# Adafruit_Pro_Trinket_5v0.net
KiCad netlist of a schematic drawn in EAGLE
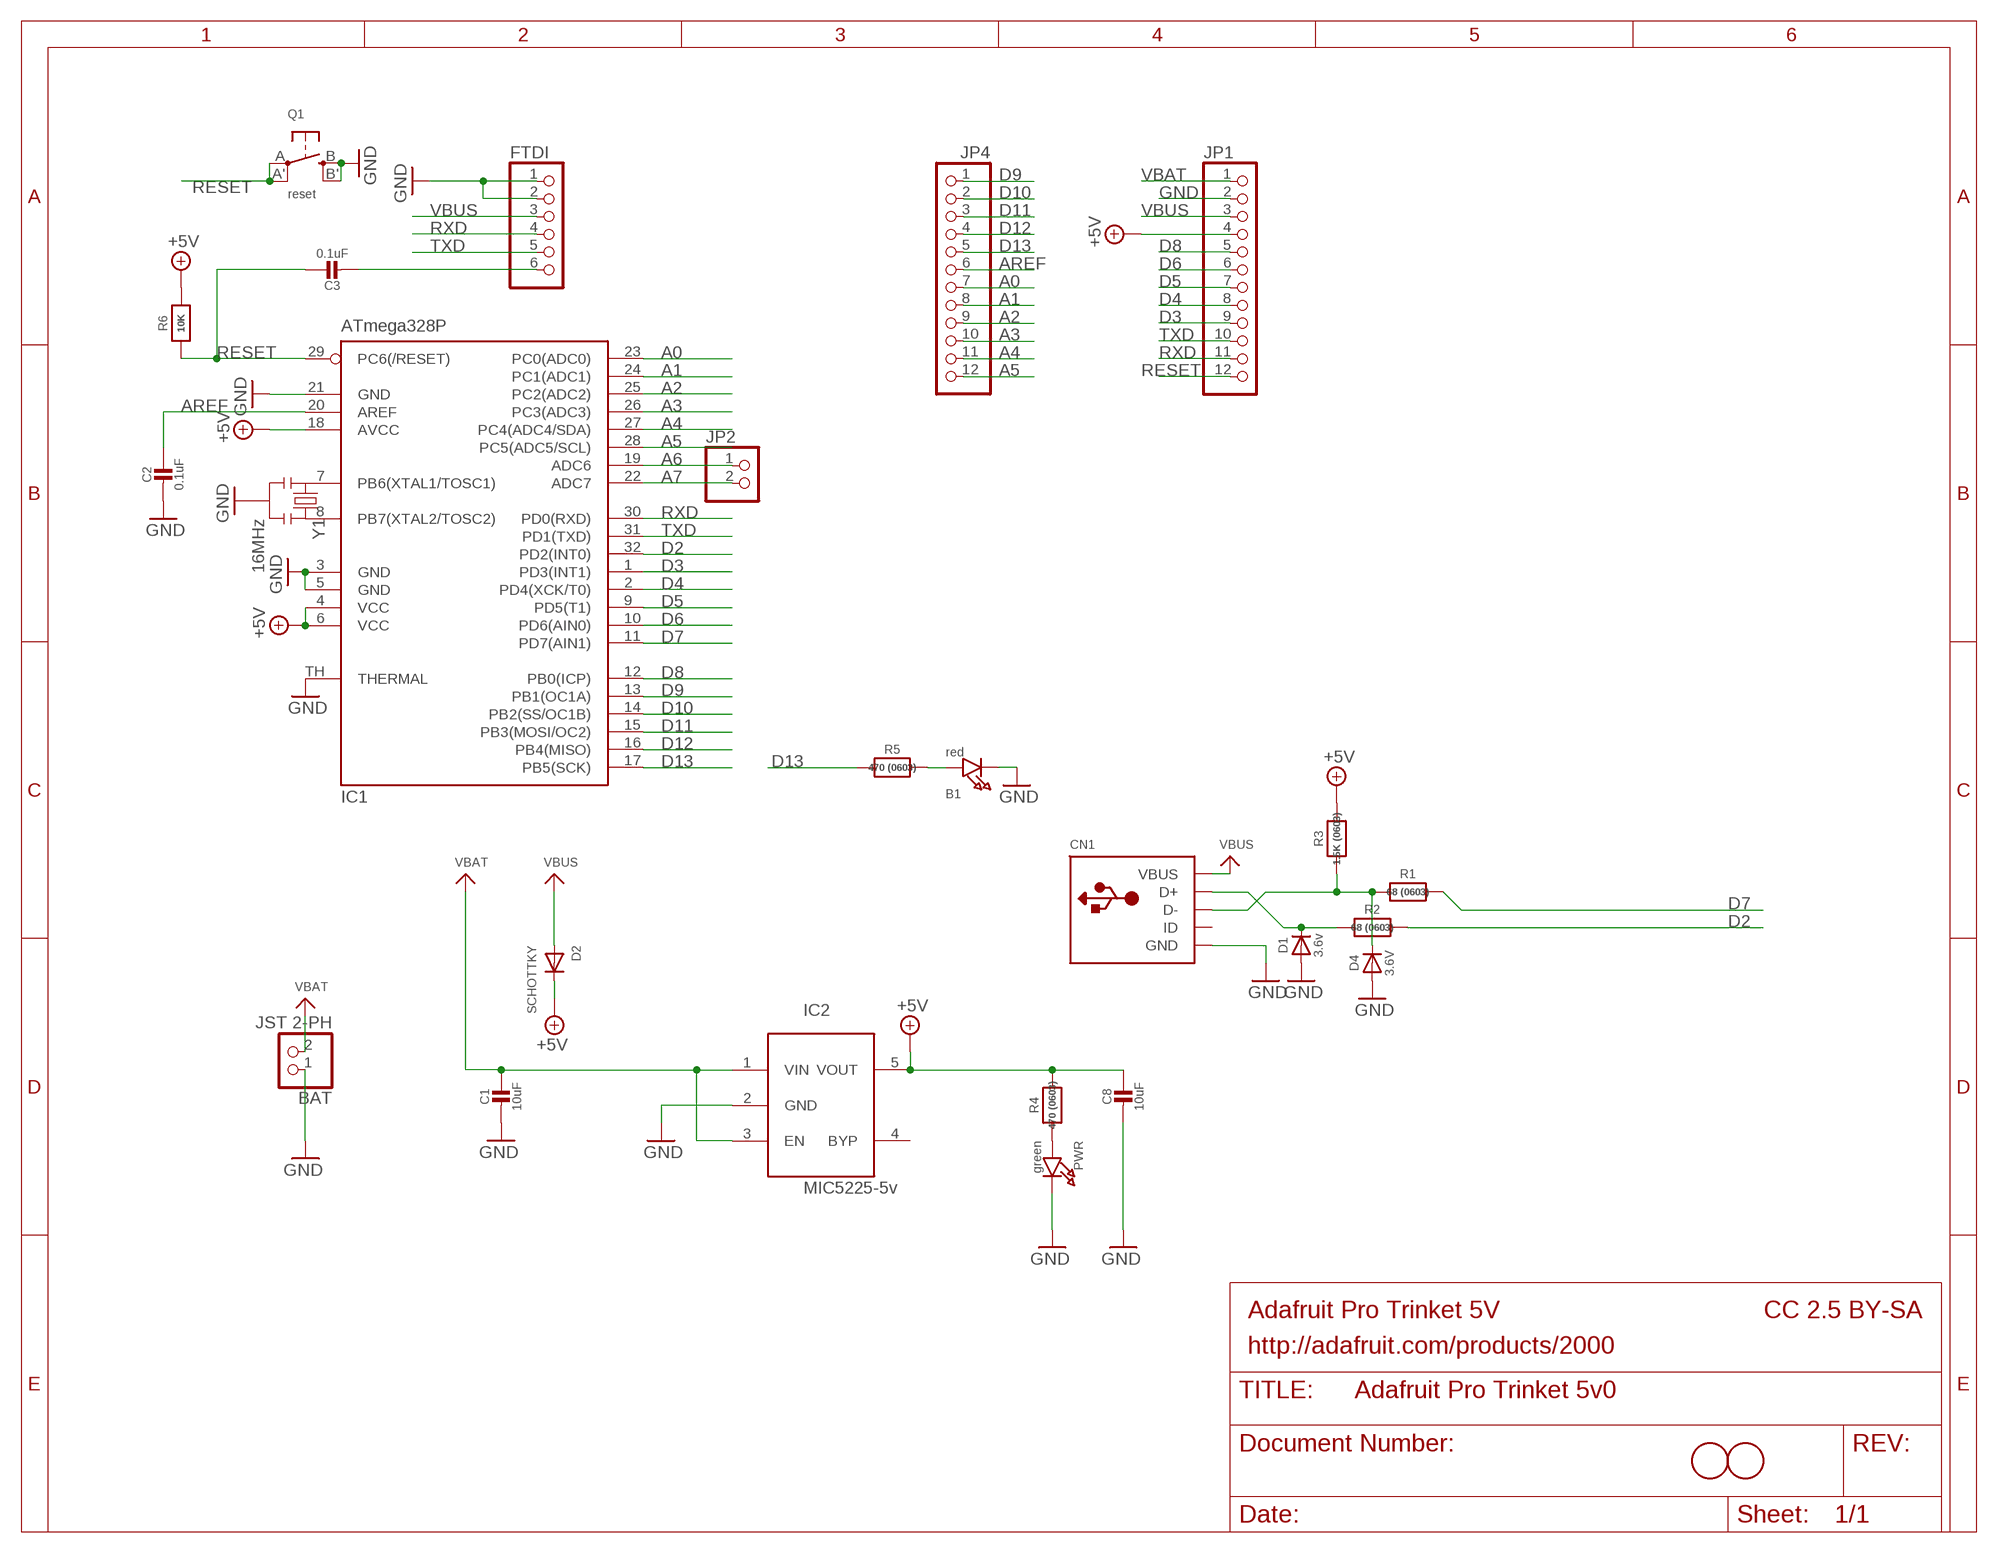
[diagram p0: schematic, sheet 1]

(export (version "E")
  (design (tool "Eeschema 10.0.6"))
  (components
    (comp (ref "B1")
      (value "red")
      (footprint "eagle-import:CHIPLED_0805_NOOUTLINE")
      (libsource (lib "eagle-import") (part "LED0805_NOOUTLINE"))
    )
    (comp (ref "BAT")
      (value "JST 2-PH")
      (footprint "eagle-import:JSTPH2")
      (libsource (lib "eagle-import") (part "CON_JST_PH_2PIN"))
    )
    (comp (ref "C1")
      (value "10uF")
      (footprint "eagle-import:0805-NO")
      (libsource (lib "eagle-import") (part "CAP_CERAMIC0805-NOOUTLINE"))
    )
    (comp (ref "C2")
      (value "0.1uF")
      (footprint "eagle-import:_0805MP")
      (libsource (lib "eagle-import") (part "CAP_CERAMIC_0805MP"))
    )
    (comp (ref "C3")
      (value "0.1uF")
      (footprint "eagle-import:0805-NO")
      (libsource (lib "eagle-import") (part "CAP_CERAMIC0805-NOOUTLINE"))
    )
    (comp (ref "C8")
      (value "10uF")
      (footprint "eagle-import:0805-NO")
      (libsource (lib "eagle-import") (part "CAP_CERAMIC0805-NOOUTLINE"))
    )
    (comp (ref "CN1")
      (value "USBMICRO_20329")
      (footprint "eagle-import:4UCONN_20329")
      (libsource (lib "eagle-import") (part "USBMICRO_20329"))
    )
    (comp (ref "D1")
      (value "3.6v")
      (footprint "eagle-import:SOD-323")
      (libsource (lib "eagle-import") (part "DIODESOD-323"))
    )
    (comp (ref "D2")
      (value "SCHOTTKY")
      (footprint "eagle-import:SOD-123FL")
      (libsource (lib "eagle-import") (part "DIODE_SOD-123FL"))
    )
    (comp (ref "D4")
      (value "3.6V")
      (footprint "eagle-import:SOD-323")
      (libsource (lib "eagle-import") (part "DIODESOD-323"))
    )
    (comp (ref "FTDI")
      (value "PINHD-1X6CB")
      (footprint "eagle-import:1X06-CLEANBIG")
      (libsource (lib "eagle-import") (part "PINHD-1X6CB"))
    )
    (comp (ref "IC1")
      (value "ATmega328P")
      (footprint "eagle-import:MLF32-TH")
      (fields (field (name "MPN") "ATMEGA88PA-MU"))
      (libsource (lib "eagle-import") (part "MEGA8-MI"))
    )
    (comp (ref "IC2")
      (value "MIC5225-5v")
      (footprint "eagle-import:SOT23-5L")
      (libsource (lib "eagle-import") (part "LP298XS"))
    )
    (comp (ref "JP1")
      (value "PINHD-1X12-CB")
      (footprint "eagle-import:1X12-CB")
      (libsource (lib "eagle-import") (part "PINHD-1X12-CB"))
    )
    (comp (ref "JP2")
      (value "HEADER-1X2ROUND")
      (footprint "eagle-import:1X02_ROUND")
      (libsource (lib "eagle-import") (part "HEADER-1X2ROUND"))
    )
    (comp (ref "JP4")
      (value "PINHD-1X12-CB")
      (footprint "eagle-import:1X12-CB")
      (libsource (lib "eagle-import") (part "PINHD-1X12-CB"))
    )
    (comp (ref "PWR")
      (value "green")
      (footprint "eagle-import:CHIPLED_0805_NOOUTLINE")
      (libsource (lib "eagle-import") (part "LED0805_NOOUTLINE"))
    )
    (comp (ref "Q1")
      (value "reset")
      (footprint "eagle-import:BTN_KMR2_4.6X2.8")
      (libsource (lib "eagle-import") (part "SWITCH_TACT_SMT4.6X2.8"))
    )
    (comp (ref "R1")
      (value "68 (0603)")
      (footprint "eagle-import:0603-NO")
      (libsource (lib "eagle-import") (part "RESISTOR_0603_NOOUT"))
    )
    (comp (ref "R2")
      (value "68 (0603)")
      (footprint "eagle-import:0603-NO")
      (libsource (lib "eagle-import") (part "RESISTOR_0603_NOOUT"))
    )
    (comp (ref "R3")
      (value "1.5K (0603)")
      (footprint "eagle-import:0603-NO")
      (libsource (lib "eagle-import") (part "RESISTOR_0603_NOOUT"))
    )
    (comp (ref "R4")
      (value "470 (0603)")
      (footprint "eagle-import:0603-NO")
      (libsource (lib "eagle-import") (part "RESISTOR_0603_NOOUT"))
    )
    (comp (ref "R5")
      (value "470 (0603)")
      (footprint "eagle-import:0603-NO")
      (libsource (lib "eagle-import") (part "RESISTOR_0603_NOOUT"))
    )
    (comp (ref "R6")
      (value "10K")
      (footprint "eagle-import:0805-NO")
      (libsource (lib "eagle-import") (part "RESISTOR0805_NOOUTLINE"))
    )
    (comp (ref "U$1")
      (value "FIDUCIAL")
      (footprint "eagle-import:FIDUCIAL_1MM")
      (libsource (lib "eagle-import") (part "FIDUCIAL"))
    )
    (comp (ref "U$6")
      (value "FIDUCIAL")
      (footprint "eagle-import:FIDUCIAL_1MM")
      (libsource (lib "eagle-import") (part "FIDUCIAL"))
    )
    (comp (ref "Y1")
      (value "16MHz")
      (footprint "eagle-import:RESONATOR-SMD")
      (libsource (lib "eagle-import") (part "RESONATORSMD"))
    )
  )
  (nets
    (net (code "1") (name "+5V") (class "Default")
      (node (ref "C8") (pin "1") (pinfunction "1_1") (pintype "passive"))
      (node (ref "D2") (pin "C") (pinfunction "C_C") (pintype "passive"))
      (node (ref "IC1") (pin "18") (pinfunction "AVCC_18") (pintype "power_in"))
      (node (ref "IC1") (pin "4") (pinfunction "VCC_4") (pintype "power_in"))
      (node (ref "IC1") (pin "6") (pinfunction "VCC_6") (pintype "power_in"))
      (node (ref "IC2") (pin "5") (pinfunction "VOUT_5") (pintype "bidirectional"))
      (node (ref "JP1") (pin "4") (pinfunction "4_4") (pintype "passive"))
      (node (ref "R3") (pin "2") (pinfunction "2_2") (pintype "passive"))
      (node (ref "R4") (pin "2") (pinfunction "2_2") (pintype "passive"))
      (node (ref "R6") (pin "2") (pinfunction "2_2") (pintype "passive"))
    )
    (net (code "2") (name "/A0") (class "Default")
      (node (ref "IC1") (pin "23") (pinfunction "PC0(ADC0)_23") (pintype "bidirectional"))
      (node (ref "JP4") (pin "7") (pinfunction "7_7") (pintype "passive"))
    )
    (net (code "3") (name "/A1") (class "Default")
      (node (ref "IC1") (pin "24") (pinfunction "PC1(ADC1)_24") (pintype "bidirectional"))
      (node (ref "JP4") (pin "8") (pinfunction "8_8") (pintype "passive"))
    )
    (net (code "4") (name "/A2") (class "Default")
      (node (ref "IC1") (pin "25") (pinfunction "PC2(ADC2)_25") (pintype "bidirectional"))
      (node (ref "JP4") (pin "9") (pinfunction "9_9") (pintype "passive"))
    )
    (net (code "5") (name "/A3") (class "Default")
      (node (ref "IC1") (pin "26") (pinfunction "PC3(ADC3)_26") (pintype "bidirectional"))
      (node (ref "JP4") (pin "10") (pinfunction "10_10") (pintype "passive"))
    )
    (net (code "6") (name "/A4") (class "Default")
      (node (ref "IC1") (pin "27") (pinfunction "PC4(ADC4/SDA)_27") (pintype "bidirectional"))
      (node (ref "JP4") (pin "11") (pinfunction "11_11") (pintype "passive"))
    )
    (net (code "7") (name "/A5") (class "Default")
      (node (ref "IC1") (pin "28") (pinfunction "PC5(ADC5/SCL)_28") (pintype "bidirectional"))
      (node (ref "JP4") (pin "12") (pinfunction "12_12") (pintype "passive"))
    )
    (net (code "8") (name "/A6") (class "Default")
      (node (ref "IC1") (pin "19") (pinfunction "ADC6_19") (pintype "bidirectional"))
      (node (ref "JP2") (pin "1") (pinfunction "1_1") (pintype "passive"))
    )
    (net (code "9") (name "/A7") (class "Default")
      (node (ref "IC1") (pin "22") (pinfunction "ADC7_22") (pintype "bidirectional"))
      (node (ref "JP2") (pin "2") (pinfunction "2_2") (pintype "passive"))
    )
    (net (code "10") (name "/AREF") (class "Default")
      (node (ref "C2") (pin "1") (pinfunction "1_1") (pintype "passive"))
      (node (ref "IC1") (pin "20") (pinfunction "AREF_20") (pintype "passive"))
      (node (ref "JP4") (pin "6") (pinfunction "6_6") (pintype "passive"))
    )
    (net (code "11") (name "/D2") (class "Default")
      (node (ref "IC1") (pin "32") (pinfunction "PD2(INT0)_32") (pintype "bidirectional"))
      (node (ref "R2") (pin "2") (pinfunction "2_2") (pintype "passive"))
    )
    (net (code "12") (name "/D3") (class "Default")
      (node (ref "IC1") (pin "1") (pinfunction "PD3(INT1)_1") (pintype "bidirectional"))
      (node (ref "JP1") (pin "9") (pinfunction "9_9") (pintype "passive"))
    )
    (net (code "13") (name "/D4") (class "Default")
      (node (ref "IC1") (pin "2") (pinfunction "PD4(XCK/T0)_2") (pintype "bidirectional"))
      (node (ref "JP1") (pin "8") (pinfunction "8_8") (pintype "passive"))
    )
    (net (code "14") (name "/D5") (class "Default")
      (node (ref "IC1") (pin "9") (pinfunction "PD5(T1)_9") (pintype "bidirectional"))
      (node (ref "JP1") (pin "7") (pinfunction "7_7") (pintype "passive"))
    )
    (net (code "15") (name "/D6") (class "Default")
      (node (ref "IC1") (pin "10") (pinfunction "PD6(AIN0)_10") (pintype "bidirectional"))
      (node (ref "JP1") (pin "6") (pinfunction "6_6") (pintype "passive"))
    )
    (net (code "16") (name "/D7") (class "Default")
      (node (ref "IC1") (pin "11") (pinfunction "PD7(AIN1)_11") (pintype "bidirectional"))
      (node (ref "R1") (pin "2") (pinfunction "2_2") (pintype "passive"))
    )
    (net (code "17") (name "/D8") (class "Default")
      (node (ref "IC1") (pin "12") (pinfunction "PB0(ICP)_12") (pintype "bidirectional"))
      (node (ref "JP1") (pin "5") (pinfunction "5_5") (pintype "passive"))
    )
    (net (code "18") (name "/D9") (class "Default")
      (node (ref "IC1") (pin "13") (pinfunction "PB1(OC1A)_13") (pintype "bidirectional"))
      (node (ref "JP4") (pin "1") (pinfunction "1_1") (pintype "passive"))
    )
    (net (code "19") (name "/D10") (class "Default")
      (node (ref "IC1") (pin "14") (pinfunction "PB2(SS/OC1B)_14") (pintype "bidirectional"))
      (node (ref "JP4") (pin "2") (pinfunction "2_2") (pintype "passive"))
    )
    (net (code "20") (name "/D11") (class "Default")
      (node (ref "IC1") (pin "15") (pinfunction "PB3(MOSI/OC2)_15") (pintype "bidirectional"))
      (node (ref "JP4") (pin "3") (pinfunction "3_3") (pintype "passive"))
    )
    (net (code "21") (name "/D12") (class "Default")
      (node (ref "IC1") (pin "16") (pinfunction "PB4(MISO)_16") (pintype "bidirectional"))
      (node (ref "JP4") (pin "4") (pinfunction "4_4") (pintype "passive"))
    )
    (net (code "22") (name "/D13") (class "Default")
      (node (ref "IC1") (pin "17") (pinfunction "PB5(SCK)_17") (pintype "bidirectional"))
      (node (ref "JP4") (pin "5") (pinfunction "5_5") (pintype "passive"))
      (node (ref "R5") (pin "2") (pinfunction "2_2") (pintype "passive"))
    )
    (net (code "23") (name "/RESET") (class "Default")
      (node (ref "C3") (pin "1") (pinfunction "1_1") (pintype "passive"))
      (node (ref "IC1") (pin "29") (pinfunction "PC6(/RESET)_29") (pintype "bidirectional"))
      (node (ref "JP1") (pin "12") (pinfunction "12_12") (pintype "passive"))
      (node (ref "Q1") (pin "A") (pinfunction "P_A") (pintype "passive"))
      (node (ref "Q1") (pin "A'") (pinfunction "P1_A'") (pintype "passive"))
      (node (ref "R6") (pin "1") (pinfunction "1_1") (pintype "passive"))
    )
    (net (code "24") (name "/RXD") (class "Default")
      (node (ref "FTDI") (pin "4") (pinfunction "4_4") (pintype "passive"))
      (node (ref "IC1") (pin "30") (pinfunction "PD0(RXD)_30") (pintype "bidirectional"))
      (node (ref "JP1") (pin "11") (pinfunction "11_11") (pintype "passive"))
    )
    (net (code "25") (name "/TXD") (class "Default")
      (node (ref "FTDI") (pin "5") (pinfunction "5_5") (pintype "passive"))
      (node (ref "IC1") (pin "31") (pinfunction "PD1(TXD)_31") (pintype "bidirectional"))
      (node (ref "JP1") (pin "10") (pinfunction "10_10") (pintype "passive"))
    )
    (net (code "26") (name "GND") (class "Default")
      (node (ref "B1") (pin "C") (pinfunction "C_C") (pintype "passive"))
      (node (ref "BAT") (pin "1") (pinfunction "1_1") (pintype "passive"))
      (node (ref "C1") (pin "2") (pinfunction "2_2") (pintype "passive"))
      (node (ref "C2") (pin "2") (pinfunction "2_2") (pintype "passive"))
      (node (ref "C8") (pin "2") (pinfunction "2_2") (pintype "passive"))
      (node (ref "CN1") (pin "BASE@1") (pinfunction "GND_BASE@1") (pintype "power_in"))
      (node (ref "CN1") (pin "BASE@2") (pinfunction "GND_BASE@2") (pintype "power_in"))
      (node (ref "CN1") (pin "GND") (pinfunction "GND_GND") (pintype "power_in"))
      (node (ref "CN1") (pin "SPRT@1") (pinfunction "GND_SPRT@1") (pintype "power_in"))
      (node (ref "CN1") (pin "SPRT@2") (pinfunction "GND_SPRT@2") (pintype "power_in"))
      (node (ref "CN1") (pin "SPRT@3") (pinfunction "GND_SPRT@3") (pintype "power_in"))
      (node (ref "CN1") (pin "SPRT@4") (pinfunction "GND_SPRT@4") (pintype "power_in"))
      (node (ref "D1") (pin "A") (pinfunction "A_A") (pintype "passive"))
      (node (ref "D4") (pin "A") (pinfunction "A_A") (pintype "passive"))
      (node (ref "FTDI") (pin "1") (pinfunction "1_1") (pintype "passive"))
      (node (ref "FTDI") (pin "2") (pinfunction "2_2") (pintype "passive"))
      (node (ref "IC1") (pin "21") (pinfunction "GND_21") (pintype "power_in"))
      (node (ref "IC1") (pin "3") (pinfunction "GND_3") (pintype "power_in"))
      (node (ref "IC1") (pin "5") (pinfunction "GND_5") (pintype "power_in"))
      (node (ref "IC1") (pin "TH") (pinfunction "THERMAL_TH") (pintype "passive"))
      (node (ref "IC2") (pin "2") (pinfunction "GND_2") (pintype "bidirectional"))
      (node (ref "JP1") (pin "2") (pinfunction "2_2") (pintype "passive"))
      (node (ref "PWR") (pin "C") (pinfunction "C_C") (pintype "passive"))
      (node (ref "Q1") (pin "B") (pinfunction "S_B") (pintype "passive"))
      (node (ref "Q1") (pin "B'") (pinfunction "S1_B'") (pintype "passive"))
      (node (ref "Y1") (pin "2") (pinfunction "2_2") (pintype "passive"))
    )
    (net (code "27") (name "Net-(B1-PadA)") (class "Default")
      (node (ref "B1") (pin "A") (pinfunction "A_A") (pintype "passive"))
      (node (ref "R5") (pin "1") (pinfunction "1_1") (pintype "passive"))
    )
    (net (code "28") (name "Net-(C3-Pad2)") (class "Default")
      (node (ref "C3") (pin "2") (pinfunction "2_2") (pintype "passive"))
      (node (ref "FTDI") (pin "6") (pinfunction "6_6") (pintype "passive"))
    )
    (net (code "29") (name "Net-(CN1-PadD+)") (class "Default")
      (node (ref "CN1") (pin "D+") (pinfunction "D+_D+") (pintype "bidirectional"))
      (node (ref "D1") (pin "C") (pinfunction "C_C") (pintype "passive"))
      (node (ref "R2") (pin "1") (pinfunction "1_1") (pintype "passive"))
    )
    (net (code "30") (name "Net-(CN1-PadD-)") (class "Default")
      (node (ref "CN1") (pin "D-") (pinfunction "D-_D-") (pintype "bidirectional"))
      (node (ref "D4") (pin "C") (pinfunction "C_C") (pintype "passive"))
      (node (ref "R1") (pin "1") (pinfunction "1_1") (pintype "passive"))
      (node (ref "R3") (pin "1") (pinfunction "1_1") (pintype "passive"))
    )
    (net (code "31") (name "Net-(IC1-PB6(XTAL1{slash}TOSC1))") (class "Default")
      (node (ref "IC1") (pin "7") (pinfunction "PB6(XTAL1/TOSC1)_7") (pintype "bidirectional"))
      (node (ref "Y1") (pin "1") (pinfunction "1_1") (pintype "passive"))
    )
    (net (code "32") (name "Net-(IC1-PB7(XTAL2{slash}TOSC2))") (class "Default")
      (node (ref "IC1") (pin "8") (pinfunction "PB7(XTAL2/TOSC2)_8") (pintype "bidirectional"))
      (node (ref "Y1") (pin "3") (pinfunction "3_3") (pintype "passive"))
    )
    (net (code "33") (name "Net-(PWR-PadA)") (class "Default")
      (node (ref "PWR") (pin "A") (pinfunction "A_A") (pintype "passive"))
      (node (ref "R4") (pin "1") (pinfunction "1_1") (pintype "passive"))
    )
    (net (code "34") (name "VBAT") (class "Default")
      (node (ref "BAT") (pin "2") (pinfunction "2_2") (pintype "passive"))
      (node (ref "C1") (pin "1") (pinfunction "1_1") (pintype "passive"))
      (node (ref "IC2") (pin "1") (pinfunction "VIN_1") (pintype "bidirectional"))
      (node (ref "IC2") (pin "3") (pinfunction "EN_3") (pintype "bidirectional"))
      (node (ref "JP1") (pin "1") (pinfunction "1_1") (pintype "passive"))
    )
    (net (code "35") (name "VBUS") (class "Default")
      (node (ref "CN1") (pin "VBUS") (pinfunction "VBUS_VBUS") (pintype "power_in"))
      (node (ref "D2") (pin "A") (pinfunction "A_A") (pintype "passive"))
      (node (ref "FTDI") (pin "3") (pinfunction "3_3") (pintype "passive"))
      (node (ref "JP1") (pin "3") (pinfunction "3_3") (pintype "passive"))
    )
    (net (code "36") (name "unconnected-(CN1-PadID)") (class "Default")
      (node (ref "CN1") (pin "ID") (pinfunction "ID_ID") (pintype "bidirectional"))
    )
    (net (code "37") (name "unconnected-(IC2-BYP-Pad4)") (class "Default")
      (node (ref "IC2") (pin "4") (pinfunction "BYP_4") (pintype "bidirectional"))
    )
  )
)
